# h-bridge.net
KiCad netlist of a schematic drawn in EAGLE
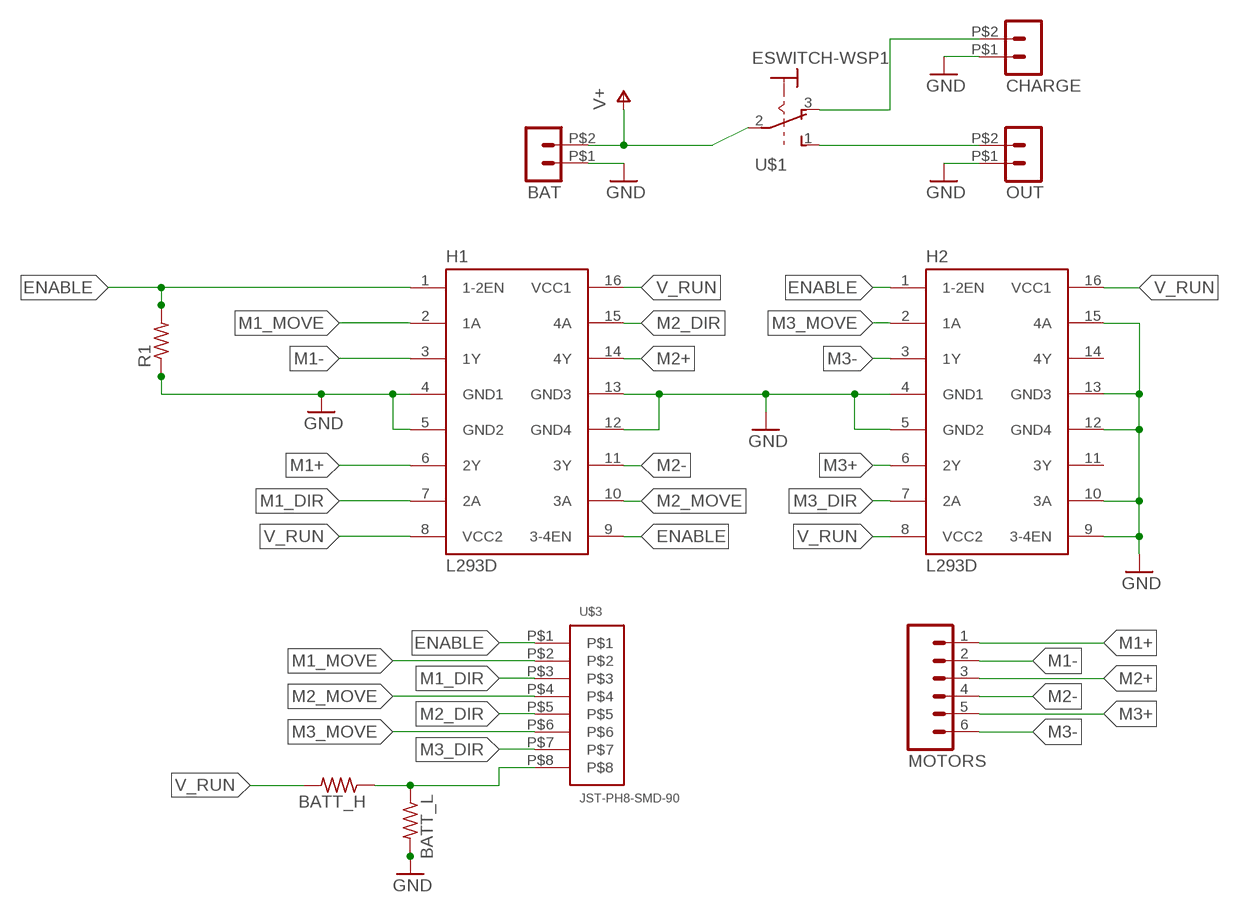
[diagram p0: schematic, sheet 1]

(export (version "E")
  (design (tool "Eeschema 10.0.6"))
  (components
    (comp (ref "BAT")
      (value "HEADER_POS2_43045-0206")
      (footprint "eagle-import:43045-0206")
      (libsource (lib "eagle-import") (part "HEADER_POS2_?43045-0206"))
    )
    (comp (ref "BATT_H")
      (value "R-US_R0603")
      (footprint "eagle-import:R0603")
      (libsource (lib "eagle-import") (part "R-US_R0603"))
    )
    (comp (ref "BATT_L")
      (value "R-US_R0603")
      (footprint "eagle-import:R0603")
      (libsource (lib "eagle-import") (part "R-US_R0603"))
    )
    (comp (ref "CHARGE")
      (value "HEADER_POS2_43045-0206")
      (footprint "eagle-import:43045-0206")
      (libsource (lib "eagle-import") (part "HEADER_POS2_?43045-0206"))
    )
    (comp (ref "H1")
      (value "L293D")
      (footprint "eagle-import:DIL16")
      (libsource (lib "eagle-import") (part "L293D"))
    )
    (comp (ref "H2")
      (value "L293D")
      (footprint "eagle-import:DIL16")
      (libsource (lib "eagle-import") (part "L293D"))
    )
    (comp (ref "MOTORS")
      (value "M06LOCK")
      (footprint "eagle-import:1X06_LOCK")
      (libsource (lib "eagle-import") (part "M06LOCK"))
    )
    (comp (ref "OUT")
      (value "HEADER_POS2_43045-0206")
      (footprint "eagle-import:43045-0206")
      (libsource (lib "eagle-import") (part "HEADER_POS2_?43045-0206"))
    )
    (comp (ref "R1")
      (value "R-US_R0603")
      (footprint "eagle-import:R0603")
      (libsource (lib "eagle-import") (part "R-US_R0603"))
    )
    (comp (ref "U$1")
      (value "ESWITCH-WSP1")
      (footprint "eagle-import:WSP1-T2-M6")
      (libsource (lib "eagle-import") (part "ESWITCH-WSP1"))
    )
    (comp (ref "U$3")
      (value "JST-PH8-SMD-90")
      (footprint "eagle-import:JST-PH-SMD-90_")
      (libsource (lib "eagle-import") (part "JST-PH8-SMD-90"))
    )
  )
  (nets
    (net (code "1") (name "ENABLE") (class "Default")
      (node (ref "H1") (pin "1") (pinfunction "1-2EN_1") (pintype "input"))
      (node (ref "H1") (pin "9") (pinfunction "3-4EN_9") (pintype "input"))
      (node (ref "H2") (pin "1") (pinfunction "1-2EN_1") (pintype "input"))
      (node (ref "R1") (pin "2") (pinfunction "2_2") (pintype "passive"))
      (node (ref "U$3") (pin "P$1") (pinfunction "P$1_P$1") (pintype "bidirectional"))
    )
    (net (code "2") (name "GND") (class "Default")
      (node (ref "BAT") (pin "P$1") (pinfunction "1_P$1") (pintype "passive"))
      (node (ref "BATT_L") (pin "2") (pinfunction "2_2") (pintype "passive"))
      (node (ref "CHARGE") (pin "P$1") (pinfunction "1_P$1") (pintype "passive"))
      (node (ref "H1") (pin "12") (pinfunction "GND4_12") (pintype "power_in"))
      (node (ref "H1") (pin "13") (pinfunction "GND3_13") (pintype "power_in"))
      (node (ref "H1") (pin "4") (pinfunction "GND1_4") (pintype "power_in"))
      (node (ref "H1") (pin "5") (pinfunction "GND2_5") (pintype "power_in"))
      (node (ref "H2") (pin "10") (pinfunction "3A_10") (pintype "input"))
      (node (ref "H2") (pin "12") (pinfunction "GND4_12") (pintype "power_in"))
      (node (ref "H2") (pin "13") (pinfunction "GND3_13") (pintype "power_in"))
      (node (ref "H2") (pin "15") (pinfunction "4A_15") (pintype "input"))
      (node (ref "H2") (pin "4") (pinfunction "GND1_4") (pintype "power_in"))
      (node (ref "H2") (pin "5") (pinfunction "GND2_5") (pintype "power_in"))
      (node (ref "H2") (pin "9") (pinfunction "3-4EN_9") (pintype "input"))
      (node (ref "OUT") (pin "P$1") (pinfunction "1_P$1") (pintype "passive"))
      (node (ref "R1") (pin "1") (pinfunction "1_1") (pintype "passive"))
    )
    (net (code "3") (name "M1+") (class "Default")
      (node (ref "H1") (pin "6") (pinfunction "2Y_6") (pintype "output"))
      (node (ref "MOTORS") (pin "1") (pinfunction "1_1") (pintype "passive"))
    )
    (net (code "4") (name "M1-") (class "Default")
      (node (ref "H1") (pin "3") (pinfunction "1Y_3") (pintype "output"))
      (node (ref "MOTORS") (pin "2") (pinfunction "2_2") (pintype "passive"))
    )
    (net (code "5") (name "M1_DIR") (class "Default")
      (node (ref "H1") (pin "7") (pinfunction "2A_7") (pintype "input"))
      (node (ref "U$3") (pin "P$3") (pinfunction "P$3_P$3") (pintype "bidirectional"))
    )
    (net (code "6") (name "M1_MOVE") (class "Default")
      (node (ref "H1") (pin "2") (pinfunction "1A_2") (pintype "input"))
      (node (ref "U$3") (pin "P$2") (pinfunction "P$2_P$2") (pintype "bidirectional"))
    )
    (net (code "7") (name "M2+") (class "Default")
      (node (ref "H1") (pin "14") (pinfunction "4Y_14") (pintype "output"))
      (node (ref "MOTORS") (pin "3") (pinfunction "3_3") (pintype "passive"))
    )
    (net (code "8") (name "M2-") (class "Default")
      (node (ref "H1") (pin "11") (pinfunction "3Y_11") (pintype "output"))
      (node (ref "MOTORS") (pin "4") (pinfunction "4_4") (pintype "passive"))
    )
    (net (code "9") (name "M2_DIR") (class "Default")
      (node (ref "H1") (pin "15") (pinfunction "4A_15") (pintype "input"))
      (node (ref "U$3") (pin "P$5") (pinfunction "P$5_P$5") (pintype "bidirectional"))
    )
    (net (code "10") (name "M2_MOVE") (class "Default")
      (node (ref "H1") (pin "10") (pinfunction "3A_10") (pintype "input"))
      (node (ref "U$3") (pin "P$4") (pinfunction "P$4_P$4") (pintype "bidirectional"))
    )
    (net (code "11") (name "M3+") (class "Default")
      (node (ref "H2") (pin "6") (pinfunction "2Y_6") (pintype "output"))
      (node (ref "MOTORS") (pin "5") (pinfunction "5_5") (pintype "passive"))
    )
    (net (code "12") (name "M3-") (class "Default")
      (node (ref "H2") (pin "3") (pinfunction "1Y_3") (pintype "output"))
      (node (ref "MOTORS") (pin "6") (pinfunction "6_6") (pintype "passive"))
    )
    (net (code "13") (name "M3_DIR") (class "Default")
      (node (ref "H2") (pin "7") (pinfunction "2A_7") (pintype "input"))
      (node (ref "U$3") (pin "P$7") (pinfunction "P$7_P$7") (pintype "bidirectional"))
    )
    (net (code "14") (name "M3_MOVE") (class "Default")
      (node (ref "H2") (pin "2") (pinfunction "1A_2") (pintype "input"))
      (node (ref "U$3") (pin "P$6") (pinfunction "P$6_P$6") (pintype "bidirectional"))
    )
    (net (code "15") (name "Net-(BATT_H-Pad1)") (class "Default")
      (node (ref "BATT_H") (pin "1") (pinfunction "1_1") (pintype "passive"))
      (node (ref "BATT_L") (pin "1") (pinfunction "1_1") (pintype "passive"))
      (node (ref "U$3") (pin "P$8") (pinfunction "P$8_P$8") (pintype "bidirectional"))
    )
    (net (code "16") (name "Net-(CHARGE-2)") (class "Default")
      (node (ref "CHARGE") (pin "P$2") (pinfunction "2_P$2") (pintype "passive"))
      (node (ref "U$1") (pin "3") (pinfunction "3_3") (pintype "passive"))
    )
    (net (code "17") (name "V+") (class "Default")
      (node (ref "BAT") (pin "P$2") (pinfunction "2_P$2") (pintype "passive"))
      (node (ref "U$1") (pin "2") (pinfunction "2_2") (pintype "passive"))
    )
    (net (code "18") (name "V_RUN") (class "Default")
      (node (ref "BATT_H") (pin "2") (pinfunction "2_2") (pintype "passive"))
      (node (ref "H1") (pin "16") (pinfunction "VCC1_16") (pintype "power_in"))
      (node (ref "H1") (pin "8") (pinfunction "VCC2_8") (pintype "power_in"))
      (node (ref "H2") (pin "16") (pinfunction "VCC1_16") (pintype "power_in"))
      (node (ref "H2") (pin "8") (pinfunction "VCC2_8") (pintype "power_in"))
      (node (ref "OUT") (pin "P$2") (pinfunction "2_P$2") (pintype "passive"))
      (node (ref "U$1") (pin "1") (pinfunction "1_1") (pintype "passive"))
    )
    (net (code "19") (name "unconnected-(H2-3Y-Pad11)") (class "Default")
      (node (ref "H2") (pin "11") (pinfunction "3Y_11") (pintype "output"))
    )
    (net (code "20") (name "unconnected-(H2-4Y-Pad14)") (class "Default")
      (node (ref "H2") (pin "14") (pinfunction "4Y_14") (pintype "output"))
    )
  )
)
